# MagnetV1_2.net
KiCad netlist of a schematic drawn in Altium Designer
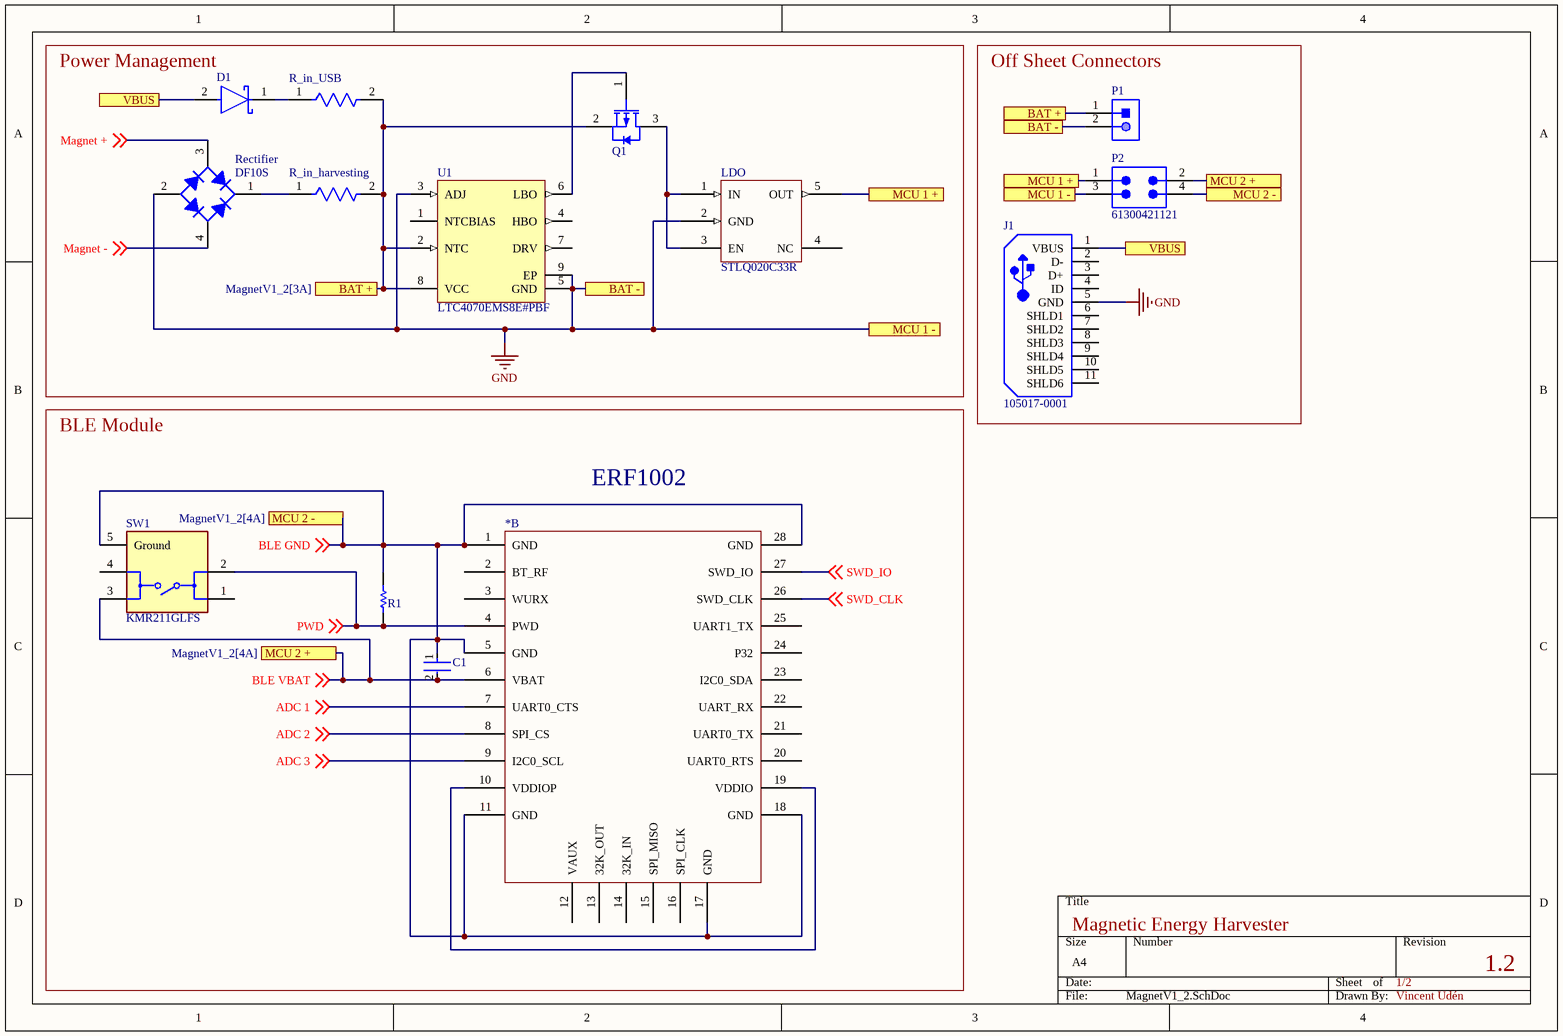
[diagram p0: MagnetV1_2.SchDoc]

(export (version "E")
  (design (tool "Eeschema 10.0.6"))
  (components
    (comp (ref "*")
      (value "ERF1002")
      (footprint "Vincent:ERF1002")
      (description "BLE Module")
      (libsource (lib "Vincent") (part "ERF1002"))
    )
    (comp (ref "C1")
      (value "TMK107B7105KA-T")
      (footprint "FP-0603-L_1_6_0_1-W_0_8_0-IPC_A")
      (description "None")
      (fields (field (name "TOLERANCE") "10%"))
      (libsource (lib "Altium Content Vault") (part "02cd4be3c70576c341d710602a673aa"))
    )
    (comp (ref "D1")
      (value "STPS1H100A")
      (footprint "FP-SMA-MFG")
      (description "DIODE SCHOTTKY 100V 1A SMA")
      (fields
        (field (name "MANUFACTURER") "STMicroelectronics")
        (field (name "OCTOPART") "https://octopart.com/stps1h100a-stmicroelectronics-55399361")
      )
      (libsource (lib "Altium Content Vault") (part "fefb30dabb5d097ae2f038500735429"))
    )
    (comp (ref "J1")
      (value "105017-0001")
      (footprint "USB-MICRO-B_V")
      (fields (field (name "MANUFACTURER") "Molex"))
      (libsource (lib "Altium Content Vault") (part "USB-5-6SHLD"))
    )
    (comp (ref "LDO")
      (value "STLQ020C33R")
      (footprint "Vincent:STLQ020CXXR")
      (description "Low-Dropout Linear Regulator 3.3 V output")
      (libsource (lib "Vincent") (part "STLQ020C33R"))
    )
    (comp (ref "P1")
      (value "S2B-PH-K-S(LF)(SN)")
      (footprint "JST-S2B-PH-K-S_V")
      (fields (field (name "TOLERANCE") "20%"))
      (libsource (lib "Altium Content Vault") (part "CN-1P-M-R2"))
    )
    (comp (ref "P2")
      (value "61300421121")
      (footprint "61300421121")
      (libsource (lib "Altium Content Vault") (part "Header_Male_2R_04P"))
    )
    (comp (ref "Q1")
      (value "NTR4171PT1G")
      (footprint "ONSC-SOT-23-3-318-08_V")
      (description "Power MOSFET, -30 V, 3.5 A, Single P-Channel, 3-Pin SOT-23, Pb-Free, Tape and Reel")
      (fields (field (name "MANUFACTURER") "On Semiconductor"))
      (libsource (lib "Altium Content Vault") (part "ONSC-PMOS-G1S2D3-3_D"))
    )
    (comp (ref "R1")
      (value "CRCW060310K0FKEA")
      (footprint "RESC1609X50X30NL8T20")
      (description "Chip Resistor, 10 KOhm, +/- 1%, 100 mW, -55 to 155 degC, 0603 (1608 Metric), RoHS, Tape and Reel")
      (fields (field (name "MANUFACTURER") "Vishay Semiconductor"))
      (libsource (lib "Altium Content Vault") (part "RES-2"))
    )
    (comp (ref "Rectifier")
      (value "DF10S")
      (footprint "FAIR-SDIP-4_V")
      (description "Bridge Rectifier, 1.5 A, 1000 V, 4-Pin SDIP, RoHS, Tape and Reel")
      (fields (field (name "MANUFACTURER") "FairchildSemiconductor"))
      (libsource (lib "Altium Content Vault") (part "D-KACC-4"))
    )
    (comp (ref "R_in_harvesting")
      (value "CRCW060310R0FKEA")
      (footprint "FP-CRCW0603-e3-IPC_A")
      (description "RES Thick Film, 10Ω, 1%, 0.1W, 100ppm/°C, 0603")
      (fields (field (name "TOLERANCE") "1%"))
      (libsource (lib "Altium Content Vault") (part "1029c3af85768c4190bb7ad29bc67b5"))
    )
    (comp (ref "R_in_USB")
      (value "CRCW060310R0FKEA")
      (footprint "FP-CRCW0603-e3-IPC_A")
      (description "RES Thick Film, 10Ω, 1%, 0.1W, 100ppm/°C, 0603")
      (fields (field (name "TOLERANCE") "1%"))
      (libsource (lib "Altium Content Vault") (part "1029c3af85768c4190bb7ad29bc67b5"))
    )
    (comp (ref "SW1")
      (value "KMR211GLFS")
      (footprint "FP-KMR211GLFS-MFG")
      (description "SWITCH TACTILE SPST-NO 0.05A 32V")
      (libsource (lib "Altium Content Vault") (part "99988cc0f9d3d39bd794ae22da860e5"))
    )
    (comp (ref "U1")
      (value "LTC4070EMS8E#PBF")
      (footprint "LT-MS8E-8-2060X1830TP_M")
      (description "Li-Ion / Polymer Shunt Battery Charger System, 8-pin SOP (MS8E-8), -40 to 125 degC, Pb-Free")
      (fields (field (name "MANUFACTURER") "Linear Technology"))
      (libsource (lib "Altium Content Vault") (part "LT-LTC4070-8"))
    )
  )
  (nets
    (net (code "1") (name "/BAT +") (class "Default")
      (node (ref "P1") (pin "1") (pinfunction "1_1") (pintype "passive"))
      (node (ref "Q1") (pin "2") (pinfunction "S_2") (pintype "passive"))
      (node (ref "R_in_USB") (pin "2") (pinfunction "2_2") (pintype "passive"))
      (node (ref "R_in_harvesting") (pin "2") (pinfunction "2_2") (pintype "passive"))
      (node (ref "U1") (pin "2") (pinfunction "NTC_2") (pintype "input"))
      (node (ref "U1") (pin "8") (pinfunction "VCC_8") (pintype "power_in"))
    )
    (net (code "2") (name "/MCU 1 +") (class "Default")
      (node (ref "LDO") (pin "5") (pinfunction "OUT_5") (pintype "output"))
      (node (ref "P2") (pin "1") (pinfunction "1_1") (pintype "passive"))
    )
    (net (code "3") (name "/VBUS") (class "Default")
      (node (ref "D1") (pin "2") (pinfunction "A_2") (pintype "passive"))
      (node (ref "J1") (pin "1") (pinfunction "VBUS_1") (pintype "passive"))
    )
    (net (code "4") (name "ADC 1") (class "Default")
      (node (ref "*") (pin "7") (pinfunction "UART0_CTS_7") (pintype "passive"))
    )
    (net (code "5") (name "ADC 2") (class "Default")
      (node (ref "*") (pin "8") (pinfunction "SPI_CS_8") (pintype "passive"))
    )
    (net (code "6") (name "ADC 3") (class "Default")
      (node (ref "*") (pin "9") (pinfunction "I2C0_SCL_9") (pintype "passive"))
    )
    (net (code "7") (name "BLE GND") (class "Default")
      (node (ref "*") (pin "1") (pinfunction "GND_1") (pintype "passive"))
      (node (ref "*") (pin "11") (pinfunction "GND_11") (pintype "passive"))
      (node (ref "*") (pin "17") (pinfunction "GND_17") (pintype "passive"))
      (node (ref "*") (pin "18") (pinfunction "GND_18") (pintype "passive"))
      (node (ref "*") (pin "28") (pinfunction "GND_28") (pintype "passive"))
      (node (ref "*") (pin "5") (pinfunction "GND_5") (pintype "passive"))
      (node (ref "C1") (pin "1") (pinfunction "1_1") (pintype "passive"))
      (node (ref "P2") (pin "4") (pinfunction "4_4") (pintype "passive"))
      (node (ref "R1") (pin "2") (pinfunction "2_2") (pintype "passive"))
      (node (ref "SW1") (pin "5") (pinfunction "Ground_5") (pintype "power_in"))
    )
    (net (code "8") (name "BLE VBAT") (class "Default")
      (node (ref "*") (pin "6") (pinfunction "VBAT_6") (pintype "passive"))
      (node (ref "C1") (pin "2") (pinfunction "2_2") (pintype "passive"))
      (node (ref "P2") (pin "2") (pinfunction "2_2") (pintype "passive"))
      (node (ref "SW1") (pin "3") (pinfunction "3_3") (pintype "passive"))
    )
    (net (code "9") (name "GND") (class "Default")
      (node (ref "J1") (pin "5") (pinfunction "GND_5") (pintype "passive"))
      (node (ref "LDO") (pin "2") (pinfunction "GND_2") (pintype "input"))
      (node (ref "P1") (pin "2") (pinfunction "2_2") (pintype "passive"))
      (node (ref "P2") (pin "3") (pinfunction "3_3") (pintype "passive"))
      (node (ref "Rectifier") (pin "2") (pinfunction "A_2") (pintype "passive"))
      (node (ref "U1") (pin "3") (pinfunction "ADJ_3") (pintype "input"))
      (node (ref "U1") (pin "5") (pinfunction "GND_5") (pintype "power_in"))
      (node (ref "U1") (pin "9") (pinfunction "EP_9") (pintype "power_in"))
    )
    (net (code "10") (name "Magnet +") (class "Default")
      (node (ref "Rectifier") (pin "3") (pinfunction "C_3") (pintype "passive"))
    )
    (net (code "11") (name "Magnet -") (class "Default")
      (node (ref "Rectifier") (pin "4") (pinfunction "C_4") (pintype "passive"))
    )
    (net (code "12") (name "Net-(*B-VDDIO)") (class "Default")
      (node (ref "*") (pin "10") (pinfunction "VDDIOP_10") (pintype "passive"))
      (node (ref "*") (pin "19") (pinfunction "VDDIO_19") (pintype "passive"))
    )
    (net (code "13") (name "Net-(D1-K)") (class "Default")
      (node (ref "D1") (pin "1") (pinfunction "K_1") (pintype "passive"))
      (node (ref "R_in_USB") (pin "1") (pinfunction "1_1") (pintype "passive"))
    )
    (net (code "14") (name "Net-(LDO-EN)") (class "Default")
      (node (ref "LDO") (pin "1") (pinfunction "IN_1") (pintype "input"))
      (node (ref "LDO") (pin "3") (pinfunction "EN_3") (pintype "passive"))
      (node (ref "Q1") (pin "3") (pinfunction "D_3") (pintype "passive"))
    )
    (net (code "15") (name "Net-(Q1-G)") (class "Default")
      (node (ref "Q1") (pin "1") (pinfunction "G_1") (pintype "passive"))
      (node (ref "U1") (pin "6") (pinfunction "LBO_6") (pintype "output"))
    )
    (net (code "16") (name "Net-(Rectifier-K)") (class "Default")
      (node (ref "R_in_harvesting") (pin "1") (pinfunction "1_1") (pintype "passive"))
      (node (ref "Rectifier") (pin "1") (pinfunction "K_1") (pintype "passive"))
    )
    (net (code "17") (name "PWD") (class "Default")
      (node (ref "*") (pin "4") (pinfunction "PWD_4") (pintype "passive"))
      (node (ref "R1") (pin "1") (pinfunction "1_1") (pintype "passive"))
      (node (ref "SW1") (pin "2") (pinfunction "2_2") (pintype "passive"))
    )
    (net (code "18") (name "SWD_CLK") (class "Default")
      (node (ref "*") (pin "26") (pinfunction "SWD_CLK_26") (pintype "passive"))
    )
    (net (code "19") (name "SWD_IO") (class "Default")
      (node (ref "*") (pin "27") (pinfunction "SWD_IO_27") (pintype "passive"))
    )
    (net (code "20") (name "unconnected-(*B-32K_IN-Pad14)") (class "Default")
      (node (ref "*") (pin "14") (pinfunction "32K_IN_14") (pintype "passive"))
    )
    (net (code "21") (name "unconnected-(*B-32K_OUT-Pad13)") (class "Default")
      (node (ref "*") (pin "13") (pinfunction "32K_OUT_13") (pintype "passive"))
    )
    (net (code "22") (name "unconnected-(*B-BT_RF-Pad2)") (class "Default")
      (node (ref "*") (pin "2") (pinfunction "BT_RF_2") (pintype "passive"))
    )
    (net (code "23") (name "unconnected-(*B-I2C0_SDA-Pad23)") (class "Default")
      (node (ref "*") (pin "23") (pinfunction "I2C0_SDA_23") (pintype "passive"))
    )
    (net (code "24") (name "unconnected-(*B-P32-Pad24)") (class "Default")
      (node (ref "*") (pin "24") (pinfunction "P32_24") (pintype "passive"))
    )
    (net (code "25") (name "unconnected-(*B-SPI_CLK-Pad16)") (class "Default")
      (node (ref "*") (pin "16") (pinfunction "SPI_CLK_16") (pintype "passive"))
    )
    (net (code "26") (name "unconnected-(*B-SPI_MISO-Pad15)") (class "Default")
      (node (ref "*") (pin "15") (pinfunction "SPI_MISO_15") (pintype "passive"))
    )
    (net (code "27") (name "unconnected-(*B-UART0_RTS-Pad20)") (class "Default")
      (node (ref "*") (pin "20") (pinfunction "UART0_RTS_20") (pintype "passive"))
    )
    (net (code "28") (name "unconnected-(*B-UART0_TX-Pad21)") (class "Default")
      (node (ref "*") (pin "21") (pinfunction "UART0_TX_21") (pintype "passive"))
    )
    (net (code "29") (name "unconnected-(*B-UART1_TX-Pad25)") (class "Default")
      (node (ref "*") (pin "25") (pinfunction "UART1_TX_25") (pintype "passive"))
    )
    (net (code "30") (name "unconnected-(*B-UART_RX-Pad22)") (class "Default")
      (node (ref "*") (pin "22") (pinfunction "UART_RX_22") (pintype "passive"))
    )
    (net (code "31") (name "unconnected-(*B-VAUX-Pad12)") (class "Default")
      (node (ref "*") (pin "12") (pinfunction "VAUX_12") (pintype "passive"))
    )
    (net (code "32") (name "unconnected-(*B-WURX-Pad3)") (class "Default")
      (node (ref "*") (pin "3") (pinfunction "WURX_3") (pintype "passive"))
    )
    (net (code "33") (name "unconnected-(J1-D+-Pad3)") (class "Default")
      (node (ref "J1") (pin "3") (pinfunction "D+_3") (pintype "passive"))
    )
    (net (code "34") (name "unconnected-(J1-D--Pad2)") (class "Default")
      (node (ref "J1") (pin "2") (pinfunction "D-_2") (pintype "passive"))
    )
    (net (code "35") (name "unconnected-(J1-ID-Pad4)") (class "Default")
      (node (ref "J1") (pin "4") (pinfunction "ID_4") (pintype "passive"))
    )
    (net (code "36") (name "unconnected-(J1-SHLD1-Pad6)") (class "Default")
      (node (ref "J1") (pin "6") (pinfunction "SHLD1_6") (pintype "passive"))
    )
    (net (code "37") (name "unconnected-(J1-SHLD2-Pad7)") (class "Default")
      (node (ref "J1") (pin "7") (pinfunction "SHLD2_7") (pintype "passive"))
    )
    (net (code "38") (name "unconnected-(J1-SHLD3-Pad8)") (class "Default")
      (node (ref "J1") (pin "8") (pinfunction "SHLD3_8") (pintype "passive"))
    )
    (net (code "39") (name "unconnected-(J1-SHLD4-Pad9)") (class "Default")
      (node (ref "J1") (pin "9") (pinfunction "SHLD4_9") (pintype "passive"))
    )
    (net (code "40") (name "unconnected-(J1-SHLD5-Pad10)") (class "Default")
      (node (ref "J1") (pin "10") (pinfunction "SHLD5_10") (pintype "passive"))
    )
    (net (code "41") (name "unconnected-(J1-SHLD6-Pad11)") (class "Default")
      (node (ref "J1") (pin "11") (pinfunction "SHLD6_11") (pintype "passive"))
    )
    (net (code "42") (name "unconnected-(LDO-NC-Pad4)") (class "Default")
      (node (ref "LDO") (pin "4") (pinfunction "NC_4") (pintype "passive"))
    )
    (net (code "43") (name "unconnected-(SW1-Pad1)") (class "Default")
      (node (ref "SW1") (pin "1") (pinfunction "1_1") (pintype "passive"))
    )
    (net (code "44") (name "unconnected-(SW1-Pad4)") (class "Default")
      (node (ref "SW1") (pin "4") (pinfunction "4_4") (pintype "passive"))
    )
    (net (code "45") (name "unconnected-(U1-DRV-Pad7)") (class "Default")
      (node (ref "U1") (pin "7") (pinfunction "DRV_7") (pintype "output"))
    )
    (net (code "46") (name "unconnected-(U1-HBO-Pad4)") (class "Default")
      (node (ref "U1") (pin "4") (pinfunction "HBO_4") (pintype "output"))
    )
    (net (code "47") (name "unconnected-(U1-NTCBIAS-Pad1)") (class "Default")
      (node (ref "U1") (pin "1") (pinfunction "NTCBIAS_1") (pintype "passive"))
    )
  )
)
